# LEDs.net
KiCad netlist of a schematic drawn in Altium Designer
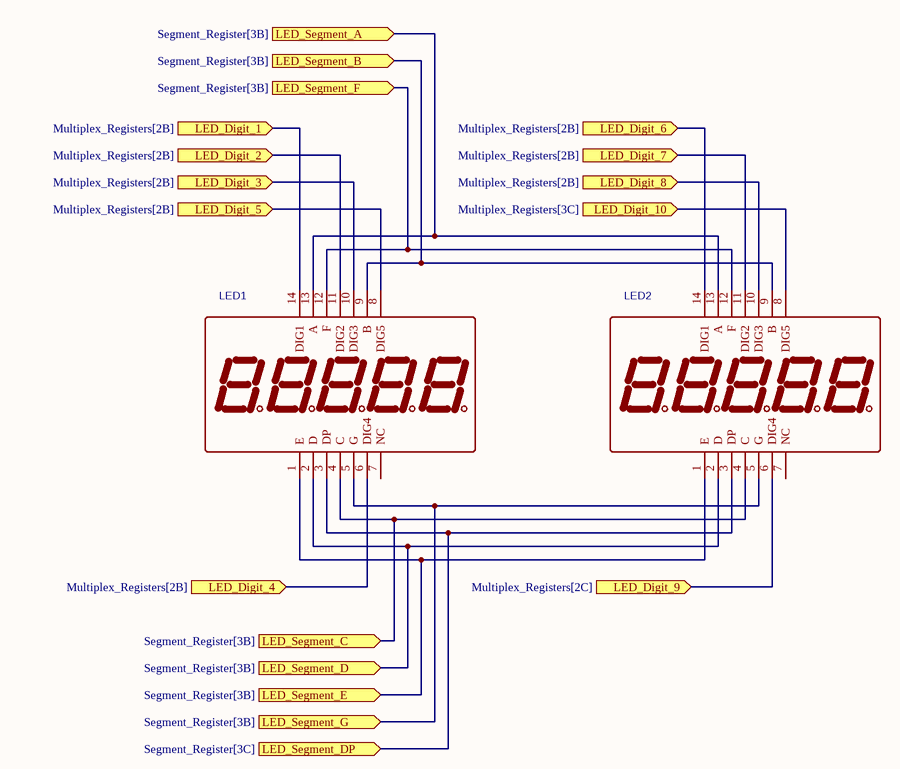
[diagram p0: LEDs.SchDoc]

(export (version "E")
  (design (tool "Eeschema 10.0.6"))
  (components
    (comp (ref "LED1")
      (value "SLR0365CRA1BD/AFN-3651A")
      (footprint "LED-SEG-TH_SLR0365CRA1BD-AFN-3651A")
      (fields (field (name "BOM_SUPPLIER PART") "C225969") (field (name "CONTRIBUTOR") "LCSC"))
      (libsource (lib "altium-import") (part "root_0_SLR0365CRA1BD/AFN-3651A_"))
    )
    (comp (ref "LED2")
      (value "SLR0365CRA1BD/AFN-3651A")
      (footprint "LED-SEG-TH_SLR0365CRA1BD-AFN-3651A")
      (fields (field (name "BOM_SUPPLIER PART") "C225969") (field (name "CONTRIBUTOR") "LCSC"))
      (libsource (lib "altium-import") (part "root_0_SLR0365CRA1BD/AFN-3651A_"))
    )
  )
  (nets
    (net (code "1") (name "/LED_Digit_1") (class "Default")
      (node (ref "LED1") (pin "14") (pinfunction "DIG1_14") (pintype "passive"))
    )
    (net (code "2") (name "/LED_Digit_2") (class "Default")
      (node (ref "LED1") (pin "11") (pinfunction "DIG2_11") (pintype "passive"))
    )
    (net (code "3") (name "/LED_Digit_3") (class "Default")
      (node (ref "LED1") (pin "10") (pinfunction "DIG3_10") (pintype "passive"))
    )
    (net (code "4") (name "/LED_Digit_4") (class "Default")
      (node (ref "LED1") (pin "6") (pinfunction "DIG4_6") (pintype "passive"))
    )
    (net (code "5") (name "/LED_Digit_5") (class "Default")
      (node (ref "LED1") (pin "8") (pinfunction "DIG5_8") (pintype "passive"))
    )
    (net (code "6") (name "/LED_Digit_6") (class "Default")
      (node (ref "LED2") (pin "14") (pinfunction "DIG1_14") (pintype "passive"))
    )
    (net (code "7") (name "/LED_Digit_7") (class "Default")
      (node (ref "LED2") (pin "11") (pinfunction "DIG2_11") (pintype "passive"))
    )
    (net (code "8") (name "/LED_Digit_8") (class "Default")
      (node (ref "LED2") (pin "10") (pinfunction "DIG3_10") (pintype "passive"))
    )
    (net (code "9") (name "/LED_Digit_9") (class "Default")
      (node (ref "LED2") (pin "6") (pinfunction "DIG4_6") (pintype "passive"))
    )
    (net (code "10") (name "/LED_Digit_10") (class "Default")
      (node (ref "LED2") (pin "8") (pinfunction "DIG5_8") (pintype "passive"))
    )
    (net (code "11") (name "/LED_Segment_A") (class "Default")
      (node (ref "LED1") (pin "13") (pinfunction "A_13") (pintype "passive"))
      (node (ref "LED2") (pin "13") (pinfunction "A_13") (pintype "passive"))
    )
    (net (code "12") (name "/LED_Segment_B") (class "Default")
      (node (ref "LED1") (pin "9") (pinfunction "B_9") (pintype "passive"))
      (node (ref "LED2") (pin "9") (pinfunction "B_9") (pintype "passive"))
    )
    (net (code "13") (name "/LED_Segment_C") (class "Default")
      (node (ref "LED1") (pin "4") (pinfunction "C_4") (pintype "passive"))
      (node (ref "LED2") (pin "4") (pinfunction "C_4") (pintype "passive"))
    )
    (net (code "14") (name "/LED_Segment_D") (class "Default")
      (node (ref "LED1") (pin "2") (pinfunction "D_2") (pintype "passive"))
      (node (ref "LED2") (pin "2") (pinfunction "D_2") (pintype "passive"))
    )
    (net (code "15") (name "/LED_Segment_DP") (class "Default")
      (node (ref "LED1") (pin "3") (pinfunction "DP_3") (pintype "passive"))
      (node (ref "LED2") (pin "3") (pinfunction "DP_3") (pintype "passive"))
    )
    (net (code "16") (name "/LED_Segment_E") (class "Default")
      (node (ref "LED1") (pin "1") (pinfunction "E_1") (pintype "passive"))
      (node (ref "LED2") (pin "1") (pinfunction "E_1") (pintype "passive"))
    )
    (net (code "17") (name "/LED_Segment_F") (class "Default")
      (node (ref "LED1") (pin "12") (pinfunction "F_12") (pintype "passive"))
      (node (ref "LED2") (pin "12") (pinfunction "F_12") (pintype "passive"))
    )
    (net (code "18") (name "/LED_Segment_G") (class "Default")
      (node (ref "LED1") (pin "5") (pinfunction "G_5") (pintype "passive"))
      (node (ref "LED2") (pin "5") (pinfunction "G_5") (pintype "passive"))
    )
    (net (code "19") (name "unconnected-(LED1-NC-Pad7)") (class "Default")
      (node (ref "LED1") (pin "7") (pinfunction "NC_7") (pintype "passive"))
    )
    (net (code "20") (name "unconnected-(LED2-NC-Pad7)") (class "Default")
      (node (ref "LED2") (pin "7") (pinfunction "NC_7") (pintype "passive"))
    )
  )
)
